# QwiicHUD.net
KiCad netlist of a schematic drawn in EAGLE
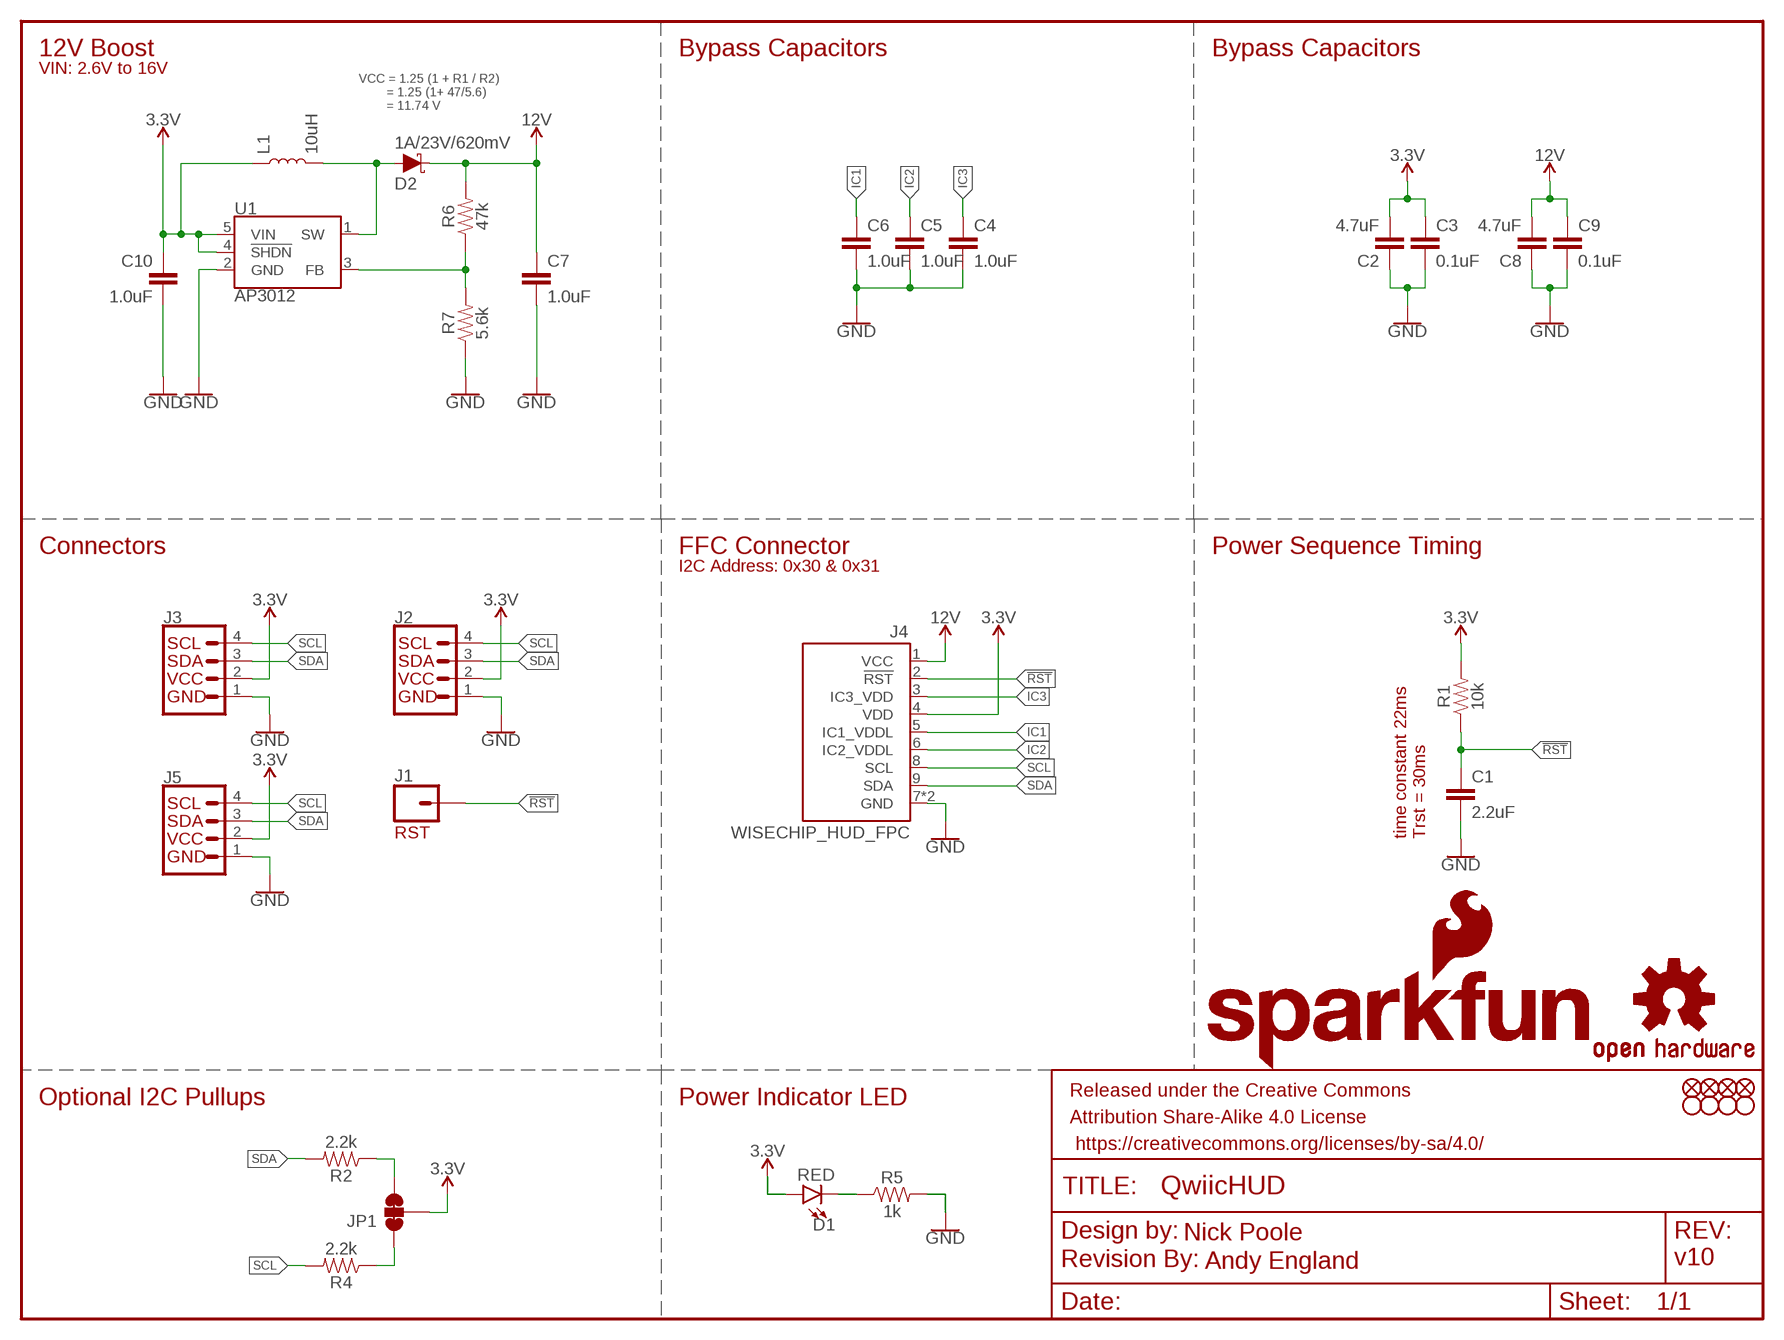
[diagram p0: schematic, sheet 1]

(export (version "E")
  (design (tool "Eeschema 10.0.6"))
  (components
    (comp (ref "C1")
      (value "2.2uF")
      (footprint "eagle-import:0603")
      (libsource (lib "eagle-import") (part "2.2UF-0603-10V-20%"))
    )
    (comp (ref "C2")
      (value "4.7uF")
      (footprint "eagle-import:0603")
      (libsource (lib "eagle-import") (part "4.7UF-0603-6.3V-(10%)"))
    )
    (comp (ref "C3")
      (value "0.1uF")
      (footprint "eagle-import:0603")
      (libsource (lib "eagle-import") (part "0.1UF-0603-25V-5%"))
    )
    (comp (ref "C4")
      (value "1.0uF")
      (footprint "eagle-import:0603")
      (libsource (lib "eagle-import") (part "1.0UF-0603-16V-10%"))
    )
    (comp (ref "C5")
      (value "1.0uF")
      (footprint "eagle-import:0603")
      (libsource (lib "eagle-import") (part "1.0UF-0603-16V-10%"))
    )
    (comp (ref "C6")
      (value "1.0uF")
      (footprint "eagle-import:0603")
      (libsource (lib "eagle-import") (part "1.0UF-0603-16V-10%"))
    )
    (comp (ref "C7")
      (value "1.0uF")
      (footprint "eagle-import:0805")
      (libsource (lib "eagle-import") (part "1.0UF-0805-25V-10%"))
    )
    (comp (ref "C8")
      (value "4.7uF")
      (footprint "eagle-import:0603")
      (libsource (lib "eagle-import") (part "4.7UF-0603-6.3V-(10%)"))
    )
    (comp (ref "C9")
      (value "0.1uF")
      (footprint "eagle-import:0603")
      (libsource (lib "eagle-import") (part "0.1UF-0603-25V-5%"))
    )
    (comp (ref "C10")
      (value "1.0uF")
      (footprint "eagle-import:0603")
      (libsource (lib "eagle-import") (part "1.0UF-0603-16V-10%"))
    )
    (comp (ref "D1")
      (value "RED")
      (footprint "eagle-import:LED-0603")
      (libsource (lib "eagle-import") (part "LED-RED0603"))
    )
    (comp (ref "D2")
      (value "1A/23V/620mV")
      (footprint "eagle-import:SOD-323")
      (libsource (lib "eagle-import") (part "DIODE-SCHOTTKY-BAT20J"))
    )
    (comp (ref "FD1")
      (value "FIDUCIALUFIDUCIAL")
      (footprint "eagle-import:FIDUCIAL-MICRO")
      (libsource (lib "eagle-import") (part "FIDUCIALUFIDUCIAL"))
    )
    (comp (ref "FD2")
      (value "FIDUCIALUFIDUCIAL")
      (footprint "eagle-import:FIDUCIAL-MICRO")
      (libsource (lib "eagle-import") (part "FIDUCIALUFIDUCIAL"))
    )
    (comp (ref "FD3")
      (value "FIDUCIALUFIDUCIAL")
      (footprint "eagle-import:FIDUCIAL-MICRO")
      (libsource (lib "eagle-import") (part "FIDUCIALUFIDUCIAL"))
    )
    (comp (ref "FD4")
      (value "FIDUCIALUFIDUCIAL")
      (footprint "eagle-import:FIDUCIAL-MICRO")
      (libsource (lib "eagle-import") (part "FIDUCIALUFIDUCIAL"))
    )
    (comp (ref "FRAME1")
      (value "FRAME-LETTER")
      (footprint "eagle-import:CREATIVE_COMMONS")
      (libsource (lib "eagle-import") (part "FRAME-LETTER"))
    )
    (comp (ref "H1")
      (value "STAND-OFF")
      (footprint "eagle-import:STAND-OFF")
      (libsource (lib "eagle-import") (part "STAND-OFF"))
    )
    (comp (ref "H2")
      (value "STAND-OFF")
      (footprint "eagle-import:STAND-OFF")
      (libsource (lib "eagle-import") (part "STAND-OFF"))
    )
    (comp (ref "H3")
      (value "STAND-OFF")
      (footprint "eagle-import:STAND-OFF")
      (libsource (lib "eagle-import") (part "STAND-OFF"))
    )
    (comp (ref "H4")
      (value "STAND-OFF")
      (footprint "eagle-import:STAND-OFF")
      (libsource (lib "eagle-import") (part "STAND-OFF"))
    )
    (comp (ref "J1")
      (value "CONN_01PTH_NO_SILK_YES_STOP")
      (footprint "eagle-import:1X01_NO_SILK")
      (libsource (lib "eagle-import") (part "CONN_01PTH_NO_SILK_YES_STOP"))
    )
    (comp (ref "J2")
      (value "I2C_STANDARD_NO_SILK")
      (footprint "eagle-import:1X04_NO_SILK")
      (libsource (lib "eagle-import") (part "I2C_STANDARD_NO_SILK"))
    )
    (comp (ref "J3")
      (value "QWIIC_CONNECTORJS-1MM")
      (footprint "eagle-import:1X04_1MM_RA")
      (libsource (lib "eagle-import") (part "QWIIC_CONNECTORJS-1MM"))
    )
    (comp (ref "J4")
      (value "WISECHIP_HUD_FPC")
      (footprint "eagle-import:SERIES6288")
      (libsource (lib "eagle-import") (part "WISECHIP_HUD_FPC"))
    )
    (comp (ref "J5")
      (value "QWIIC_CONNECTORJS-1MM")
      (footprint "eagle-import:1X04_1MM_RA")
      (libsource (lib "eagle-import") (part "QWIIC_CONNECTORJS-1MM"))
    )
    (comp (ref "JP1")
      (value "JUMPER-SMT_3_2-NC_TRACE_SILK")
      (footprint "eagle-import:SMT-JUMPER_3_2-NC_TRACE_SILK")
      (libsource (lib "eagle-import") (part "JUMPER-SMT_3_2-NC_TRACE_SILK"))
    )
    (comp (ref "L1")
      (value "10uH")
      (footprint "eagle-import:INDUCTOR_4.7UH")
      (libsource (lib "eagle-import") (part "INDUCTOR-CDRH-10UH"))
    )
    (comp (ref "LOGO1")
      (value "OSHW-LOGOS")
      (footprint "eagle-import:OSHW-LOGO-S")
      (libsource (lib "eagle-import") (part "OSHW-LOGOS"))
    )
    (comp (ref "LOGO2")
      (value "SFE_LOGO_NAME_FLAME.1_INCH")
      (footprint "eagle-import:SFE_LOGO_NAME_FLAME_.1")
      (libsource (lib "eagle-import") (part "SFE_LOGO_NAME_FLAME.1_INCH"))
    )
    (comp (ref "LOGO3")
      (value "SFE_LOGO_FLAME.1_INCH")
      (footprint "eagle-import:SFE_LOGO_FLAME_.1")
      (libsource (lib "eagle-import") (part "SFE_LOGO_FLAME.1_INCH"))
    )
    (comp (ref "LOGO4")
      (value "REVISION")
      (footprint "eagle-import:REVISION")
      (libsource (lib "eagle-import") (part "REVISION"))
    )
    (comp (ref "R1")
      (value "10k")
      (footprint "eagle-import:0603")
      (libsource (lib "eagle-import") (part "10KOHM-0603-1/10W-1%"))
    )
    (comp (ref "R2")
      (value "2.2k")
      (footprint "eagle-import:0603")
      (libsource (lib "eagle-import") (part "2.2KOHM-0603-1/10W-1%"))
    )
    (comp (ref "R4")
      (value "2.2k")
      (footprint "eagle-import:0603")
      (libsource (lib "eagle-import") (part "2.2KOHM-0603-1/10W-1%"))
    )
    (comp (ref "R5")
      (value "1k")
      (footprint "eagle-import:0603")
      (libsource (lib "eagle-import") (part "1KOHM-0603-1/10W-1%"))
    )
    (comp (ref "R6")
      (value "47k")
      (footprint "eagle-import:0603")
      (libsource (lib "eagle-import") (part "47KOHM-0603-1/10W-1%"))
    )
    (comp (ref "R7")
      (value "5.6k")
      (footprint "eagle-import:0603")
      (libsource (lib "eagle-import") (part "5.6KOHM-0603-1/10W-1%"))
    )
    (comp (ref "U1")
      (value "AP3012")
      (footprint "eagle-import:SOT23-5")
      (libsource (lib "eagle-import") (part "AP3012"))
    )
  )
  (nets
    (net (code "1") (name "/~{RST}") (class "Default")
      (node (ref "C1") (pin "1") (pinfunction "1_1") (pintype "passive"))
      (node (ref "J1") (pin "1") (pinfunction "1_1") (pintype "passive"))
      (node (ref "J4") (pin "2") (pinfunction "~{RST}_2") (pintype "bidirectional"))
      (node (ref "R1") (pin "1") (pinfunction "1_1") (pintype "passive"))
    )
    (net (code "2") (name "3.3V") (class "Default")
      (node (ref "C10") (pin "1") (pinfunction "1_1") (pintype "passive"))
      (node (ref "C2") (pin "2") (pinfunction "2_2") (pintype "passive"))
      (node (ref "C3") (pin "1") (pinfunction "1_1") (pintype "passive"))
      (node (ref "D1") (pin "A") (pinfunction "A_A") (pintype "passive"))
      (node (ref "J2") (pin "2") (pinfunction "VCC_2") (pintype "power_in"))
      (node (ref "J3") (pin "2") (pinfunction "2_2") (pintype "power_in"))
      (node (ref "J4") (pin "4") (pinfunction "VDD_4") (pintype "bidirectional"))
      (node (ref "J5") (pin "2") (pinfunction "2_2") (pintype "power_in"))
      (node (ref "JP1") (pin "2") (pinfunction "2_2") (pintype "passive"))
      (node (ref "L1") (pin "P$1") (pinfunction "1_P$1") (pintype "passive"))
      (node (ref "R1") (pin "2") (pinfunction "2_2") (pintype "passive"))
      (node (ref "U1") (pin "4") (pinfunction "~{SHDN}_4") (pintype "bidirectional"))
      (node (ref "U1") (pin "5") (pinfunction "VIN_5") (pintype "bidirectional"))
    )
    (net (code "3") (name "12V") (class "Default")
      (node (ref "C7") (pin "1") (pinfunction "1_1") (pintype "passive"))
      (node (ref "C8") (pin "2") (pinfunction "2_2") (pintype "passive"))
      (node (ref "C9") (pin "1") (pinfunction "1_1") (pintype "passive"))
      (node (ref "D2") (pin "C") (pinfunction "C_C") (pintype "passive"))
      (node (ref "J4") (pin "1") (pinfunction "VCC_1") (pintype "bidirectional"))
      (node (ref "R6") (pin "2") (pinfunction "2_2") (pintype "passive"))
    )
    (net (code "4") (name "GND") (class "Default")
      (node (ref "C1") (pin "2") (pinfunction "2_2") (pintype "passive"))
      (node (ref "C10") (pin "2") (pinfunction "2_2") (pintype "passive"))
      (node (ref "C2") (pin "1") (pinfunction "1_1") (pintype "passive"))
      (node (ref "C3") (pin "2") (pinfunction "2_2") (pintype "passive"))
      (node (ref "C4") (pin "2") (pinfunction "2_2") (pintype "passive"))
      (node (ref "C5") (pin "2") (pinfunction "2_2") (pintype "passive"))
      (node (ref "C6") (pin "2") (pinfunction "2_2") (pintype "passive"))
      (node (ref "C7") (pin "2") (pinfunction "2_2") (pintype "passive"))
      (node (ref "C8") (pin "1") (pinfunction "1_1") (pintype "passive"))
      (node (ref "C9") (pin "2") (pinfunction "2_2") (pintype "passive"))
      (node (ref "J2") (pin "1") (pinfunction "GND_1") (pintype "power_in"))
      (node (ref "J3") (pin "1") (pinfunction "1_1") (pintype "power_in"))
      (node (ref "J4") (pin "10") (pinfunction "GND_10") (pintype "bidirectional"))
      (node (ref "J4") (pin "7") (pinfunction "GND_7") (pintype "bidirectional"))
      (node (ref "J5") (pin "1") (pinfunction "1_1") (pintype "power_in"))
      (node (ref "R5") (pin "2") (pinfunction "2_2") (pintype "passive"))
      (node (ref "R7") (pin "1") (pinfunction "1_1") (pintype "passive"))
      (node (ref "U1") (pin "2") (pinfunction "GND_2") (pintype "bidirectional"))
    )
    (net (code "5") (name "IC1") (class "Default")
      (node (ref "C6") (pin "1") (pinfunction "1_1") (pintype "passive"))
      (node (ref "J4") (pin "5") (pinfunction "IC1_VDDL_5") (pintype "bidirectional"))
    )
    (net (code "6") (name "IC2") (class "Default")
      (node (ref "C5") (pin "1") (pinfunction "1_1") (pintype "passive"))
      (node (ref "J4") (pin "6") (pinfunction "IC2_VDDL_6") (pintype "bidirectional"))
    )
    (net (code "7") (name "IC3") (class "Default")
      (node (ref "C4") (pin "1") (pinfunction "1_1") (pintype "passive"))
      (node (ref "J4") (pin "3") (pinfunction "IC3_VDD_3") (pintype "bidirectional"))
    )
    (net (code "8") (name "Net-(D1-PadC)") (class "Default")
      (node (ref "D1") (pin "C") (pinfunction "C_C") (pintype "passive"))
      (node (ref "R5") (pin "1") (pinfunction "1_1") (pintype "passive"))
    )
    (net (code "9") (name "Net-(JP1-Pad1)") (class "Default")
      (node (ref "JP1") (pin "1") (pinfunction "1_1") (pintype "passive"))
      (node (ref "R4") (pin "1") (pinfunction "1_1") (pintype "passive"))
    )
    (net (code "10") (name "Net-(JP1-Pad3)") (class "Default")
      (node (ref "JP1") (pin "3") (pinfunction "3_3") (pintype "passive"))
      (node (ref "R2") (pin "1") (pinfunction "1_1") (pintype "passive"))
    )
    (net (code "11") (name "Net-(L1-2)") (class "Default")
      (node (ref "D2") (pin "A") (pinfunction "A_A") (pintype "passive"))
      (node (ref "L1") (pin "P$2") (pinfunction "2_P$2") (pintype "passive"))
      (node (ref "U1") (pin "1") (pinfunction "SW_1") (pintype "bidirectional"))
    )
    (net (code "12") (name "Net-(U1-FB)") (class "Default")
      (node (ref "R6") (pin "1") (pinfunction "1_1") (pintype "passive"))
      (node (ref "R7") (pin "2") (pinfunction "2_2") (pintype "passive"))
      (node (ref "U1") (pin "3") (pinfunction "FB_3") (pintype "bidirectional"))
    )
    (net (code "13") (name "SCL") (class "Default")
      (node (ref "J2") (pin "4") (pinfunction "SCL_4") (pintype "passive"))
      (node (ref "J3") (pin "4") (pinfunction "4_4") (pintype "passive"))
      (node (ref "J4") (pin "8") (pinfunction "SCL_8") (pintype "bidirectional"))
      (node (ref "J5") (pin "4") (pinfunction "4_4") (pintype "passive"))
      (node (ref "R4") (pin "2") (pinfunction "2_2") (pintype "passive"))
    )
    (net (code "14") (name "SDA") (class "Default")
      (node (ref "J2") (pin "3") (pinfunction "SDA_3") (pintype "passive"))
      (node (ref "J3") (pin "3") (pinfunction "3_3") (pintype "passive"))
      (node (ref "J4") (pin "9") (pinfunction "SDA_9") (pintype "bidirectional"))
      (node (ref "J5") (pin "3") (pinfunction "3_3") (pintype "passive"))
      (node (ref "R2") (pin "2") (pinfunction "2_2") (pintype "passive"))
    )
  )
)
